# pulse_generator_pth.net
KiCad netlist of a schematic drawn in EAGLE
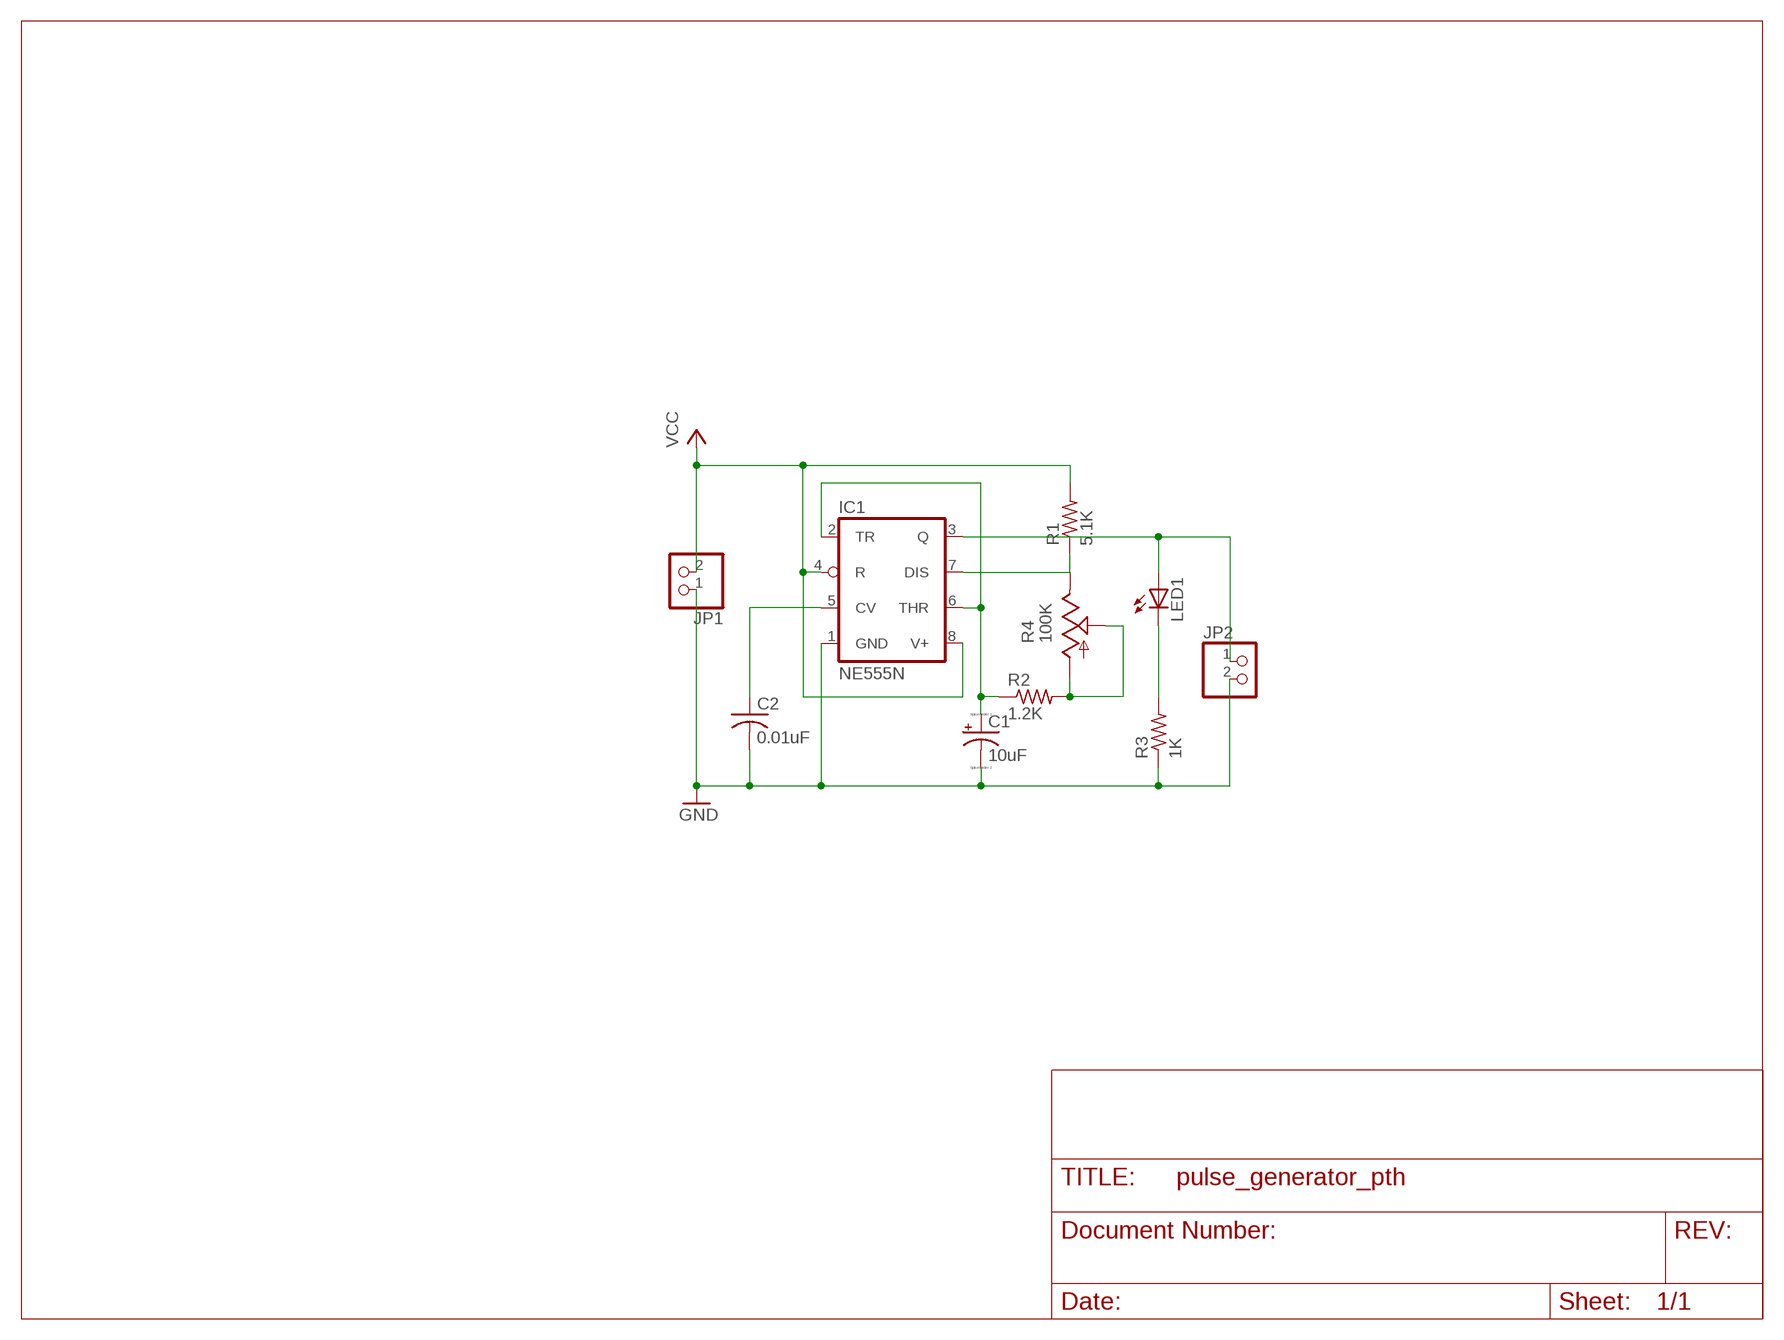
[diagram p0: schematic, sheet 1]

(export (version "E")
  (design (tool "Eeschema 10.0.6"))
  (components
    (comp (ref "C1")
      (value "10uF")
      (footprint "eagle-import:E2-5")
      (libsource (lib "eagle-import") (part "CPOL-USE2-5"))
    )
    (comp (ref "C2")
      (value "0.01uF")
      (footprint "eagle-import:C025-040X050")
      (libsource (lib "eagle-import") (part "C-US025-040X050"))
    )
    (comp (ref "IC1")
      (value "NE555N")
      (footprint "eagle-import:DIL08")
      (libsource (lib "eagle-import") (part "555NNE"))
    )
    (comp (ref "JP1")
      (value "PINHD-1X2")
      (footprint "eagle-import:1X02")
      (libsource (lib "eagle-import") (part "PINHD-1X2"))
    )
    (comp (ref "JP2")
      (value "PINHD-1X2")
      (footprint "eagle-import:1X02")
      (libsource (lib "eagle-import") (part "PINHD-1X2"))
    )
    (comp (ref "LED1")
      (value "LED5MM")
      (footprint "eagle-import:LED5MM")
      (libsource (lib "eagle-import") (part "LED5MM"))
    )
    (comp (ref "R1")
      (value "5.1K")
      (footprint "eagle-import:0204_7")
      (libsource (lib "eagle-import") (part "R-US_0204/7"))
    )
    (comp (ref "R2")
      (value "1.2K")
      (footprint "eagle-import:0204_7")
      (libsource (lib "eagle-import") (part "R-US_0204/7"))
    )
    (comp (ref "R3")
      (value "1K")
      (footprint "eagle-import:0204_7")
      (libsource (lib "eagle-import") (part "R-US_0204/7"))
    )
    (comp (ref "R4")
      (value "100K")
      (footprint "eagle-import:B25U")
      (libsource (lib "eagle-import") (part "TRIM_US-B25U"))
    )
  )
  (nets
    (net (code "1") (name "GND") (class "Default")
      (node (ref "C1") (pin "-") (pinfunction "-_-") (pintype "passive"))
      (node (ref "C2") (pin "2") (pinfunction "2_2") (pintype "passive"))
      (node (ref "IC1") (pin "1") (pinfunction "GND_1") (pintype "power_in"))
      (node (ref "JP1") (pin "1") (pinfunction "1_1") (pintype "passive"))
      (node (ref "JP2") (pin "2") (pinfunction "2_2") (pintype "passive"))
      (node (ref "R3") (pin "1") (pinfunction "1_1") (pintype "passive"))
    )
    (net (code "2") (name "Net-(IC1-CV)") (class "Default")
      (node (ref "C2") (pin "1") (pinfunction "1_1") (pintype "passive"))
      (node (ref "IC1") (pin "5") (pinfunction "CV_5") (pintype "input"))
    )
    (net (code "3") (name "Net-(IC1-DIS)") (class "Default")
      (node (ref "IC1") (pin "7") (pinfunction "DIS_7") (pintype "input"))
      (node (ref "R1") (pin "1") (pinfunction "1_1") (pintype "passive"))
      (node (ref "R4") (pin "E") (pinfunction "E_E") (pintype "passive"))
    )
    (net (code "4") (name "Net-(IC1-Q)") (class "Default")
      (node (ref "IC1") (pin "3") (pinfunction "Q_3") (pintype "output"))
      (node (ref "JP2") (pin "1") (pinfunction "1_1") (pintype "passive"))
      (node (ref "LED1") (pin "A") (pinfunction "A_A") (pintype "passive"))
    )
    (net (code "5") (name "Net-(IC1-THR)") (class "Default")
      (node (ref "C1") (pin "+") (pinfunction "+_+") (pintype "passive"))
      (node (ref "IC1") (pin "2") (pinfunction "TR_2") (pintype "input"))
      (node (ref "IC1") (pin "6") (pinfunction "THR_6") (pintype "input"))
      (node (ref "R2") (pin "1") (pinfunction "1_1") (pintype "passive"))
    )
    (net (code "6") (name "Net-(LED1-C)") (class "Default")
      (node (ref "LED1") (pin "K") (pinfunction "C_K") (pintype "passive"))
      (node (ref "R3") (pin "2") (pinfunction "2_2") (pintype "passive"))
    )
    (net (code "7") (name "Net-(R2-Pad2)") (class "Default")
      (node (ref "R2") (pin "2") (pinfunction "2_2") (pintype "passive"))
      (node (ref "R4") (pin "A") (pinfunction "A_A") (pintype "passive"))
      (node (ref "R4") (pin "S") (pinfunction "S_S") (pintype "passive"))
    )
    (net (code "8") (name "VCC") (class "Default")
      (node (ref "IC1") (pin "4") (pinfunction "R_4") (pintype "input"))
      (node (ref "IC1") (pin "8") (pinfunction "V+_8") (pintype "power_in"))
      (node (ref "JP1") (pin "2") (pinfunction "2_2") (pintype "passive"))
      (node (ref "R1") (pin "2") (pinfunction "2_2") (pintype "passive"))
    )
  )
)
